# Main-v4_1.net
KiCad netlist of a schematic drawn in EAGLE
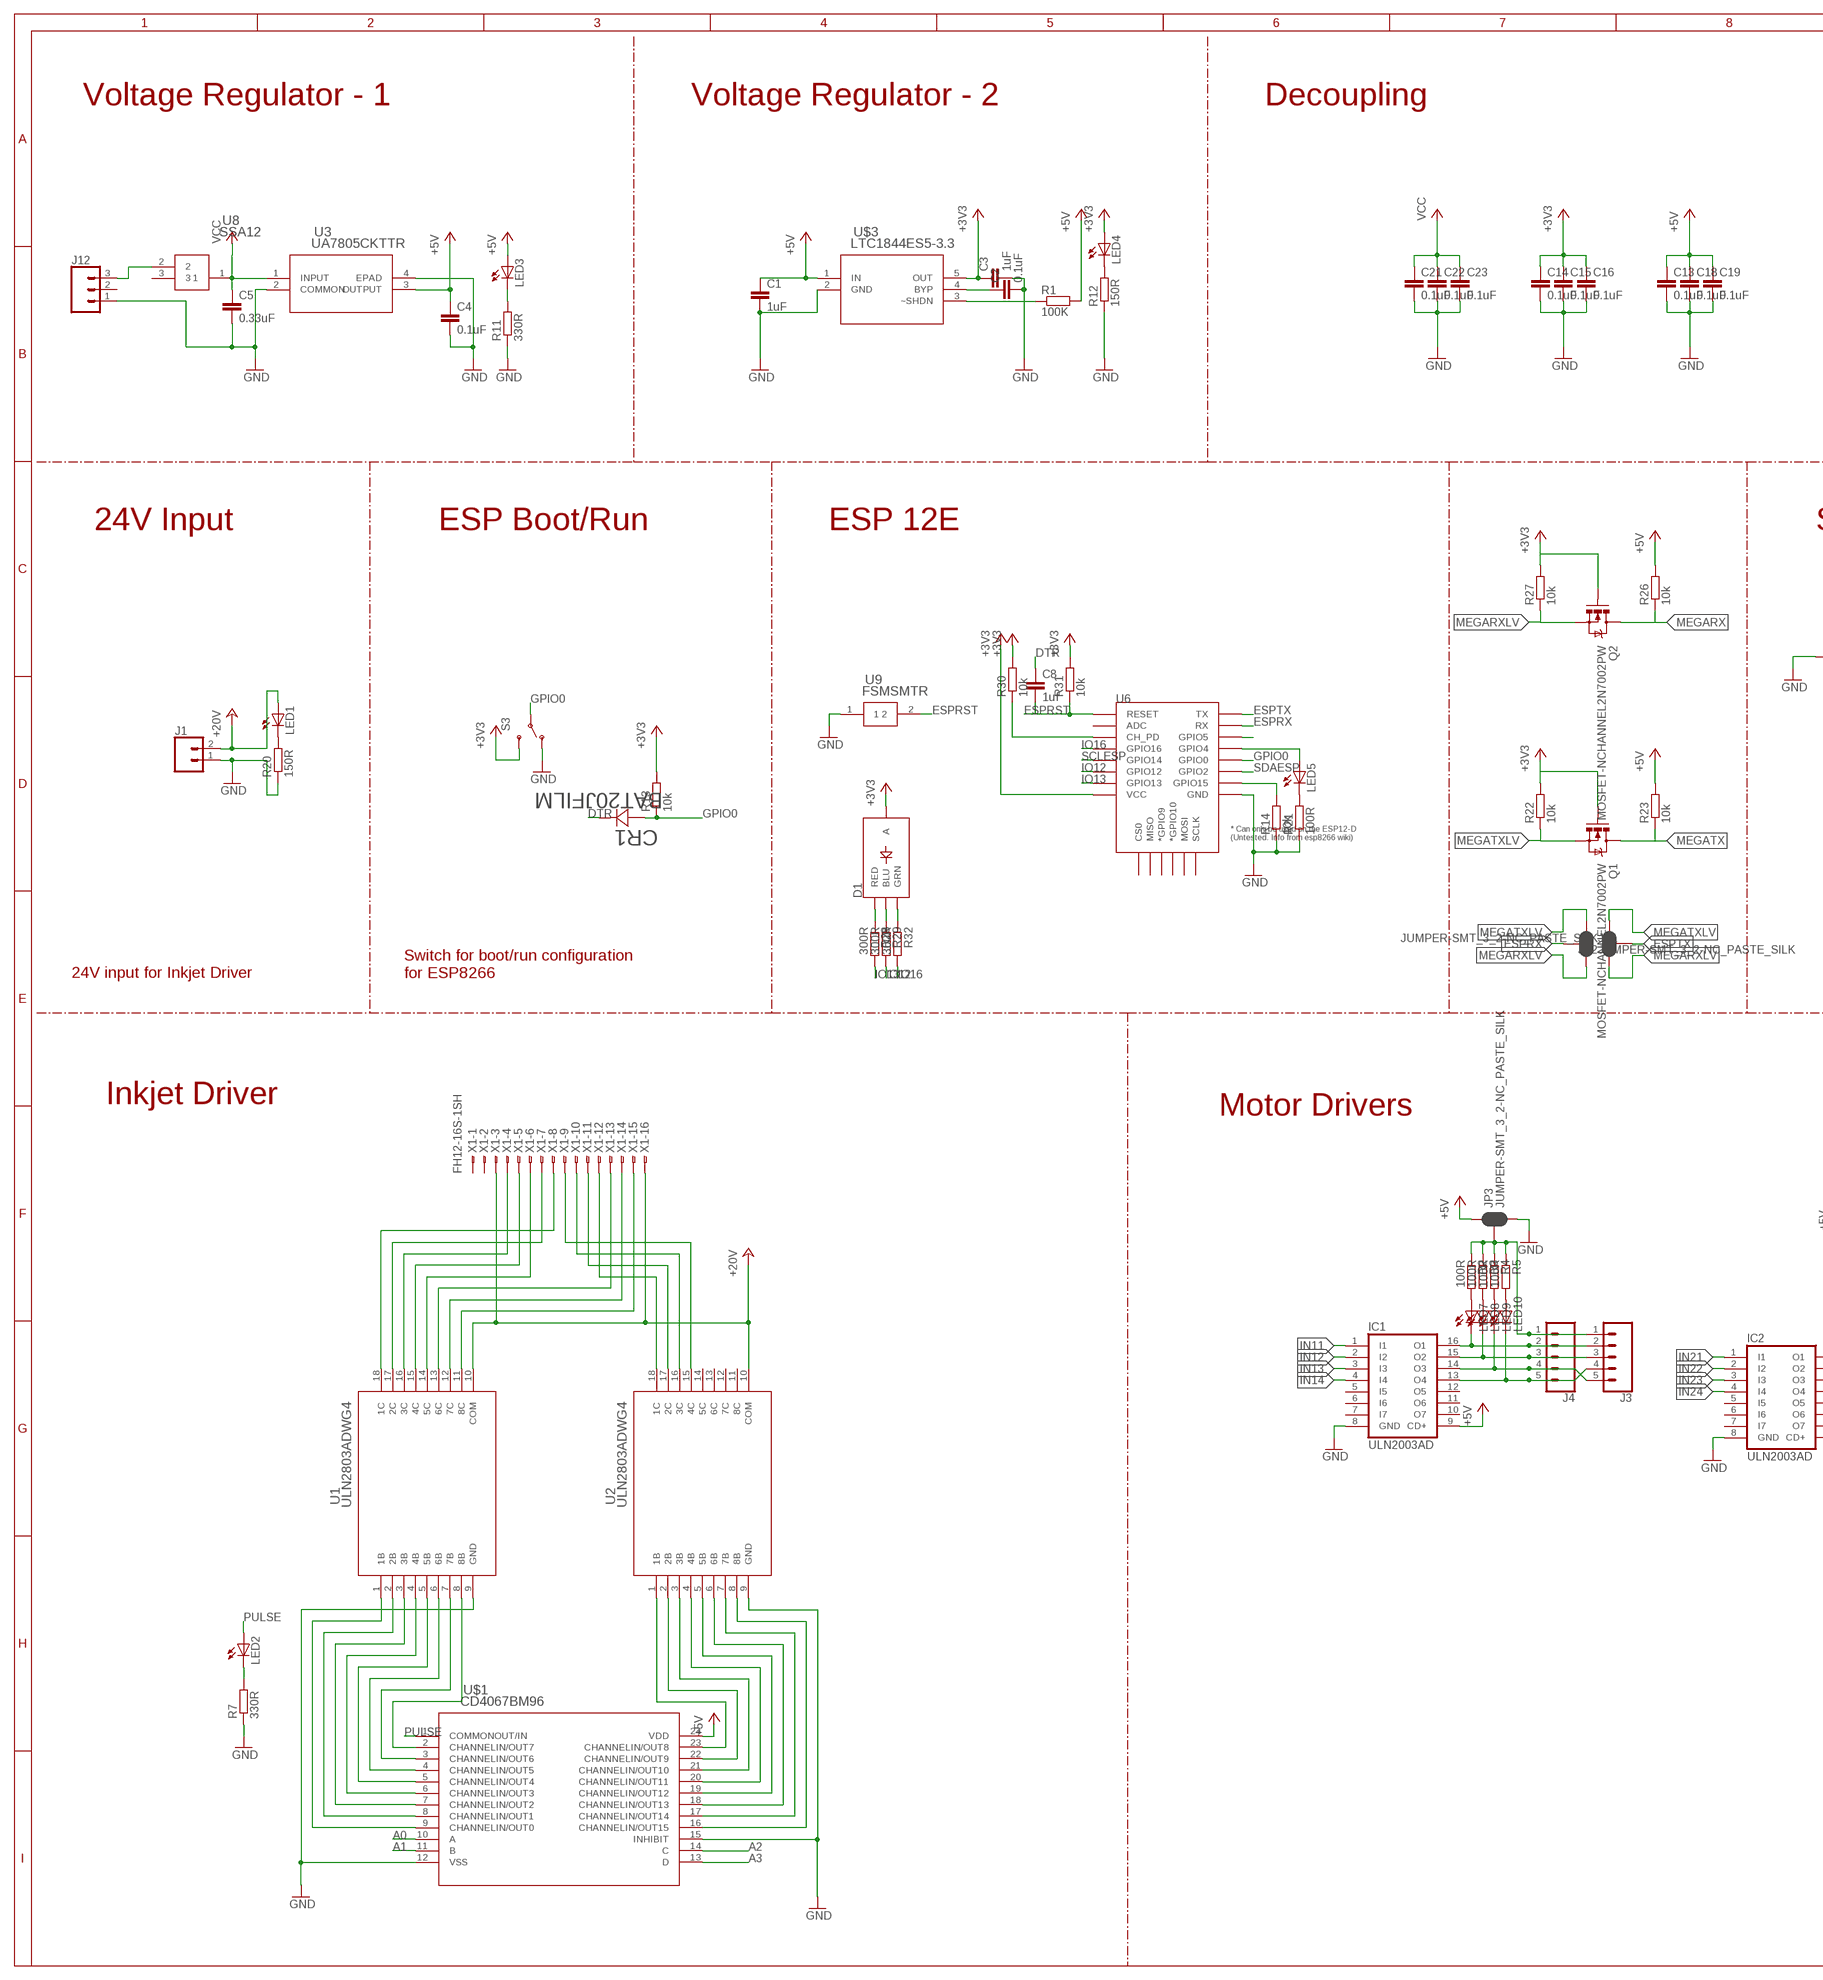
[diagram p0: schematic, sheet 1, part 1 of 3]
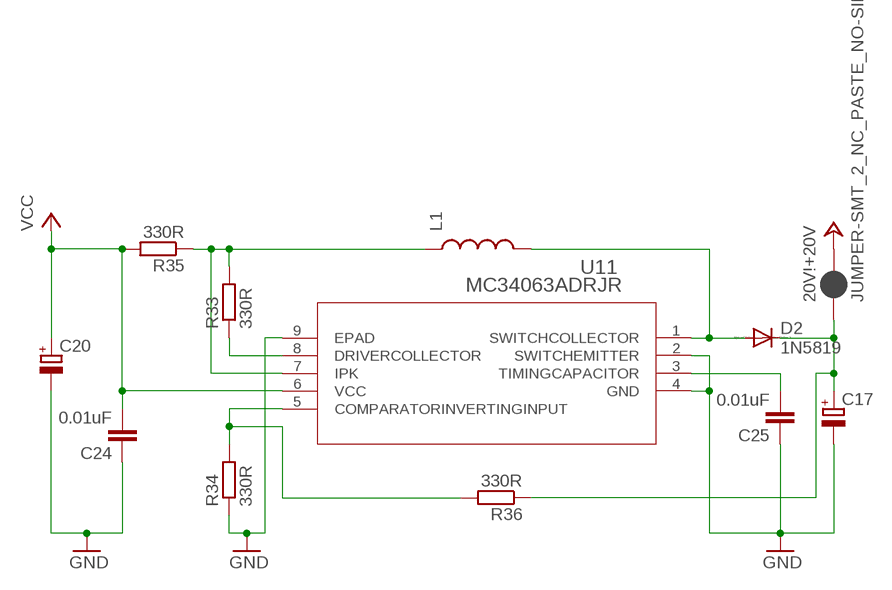
[diagram p1: schematic, sheet 1, part 2 of 3]
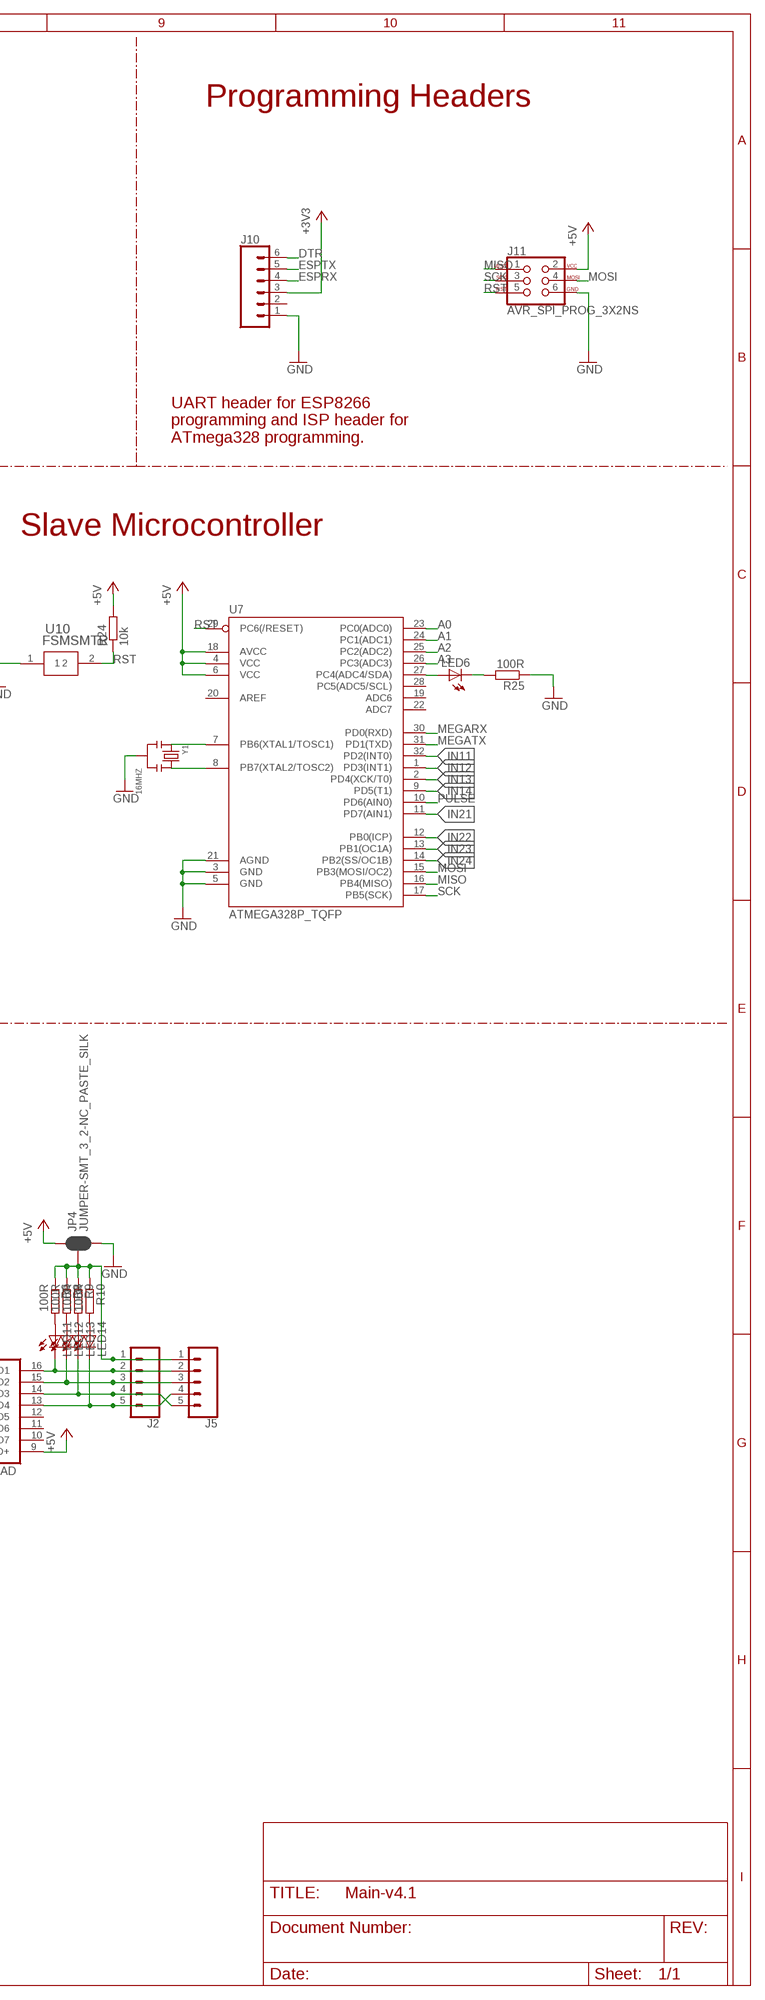
[diagram p2: schematic, sheet 1, part 3 of 3]

(export (version "E")
  (design (tool "Eeschema 10.0.6"))
  (components
    (comp (ref "20V!")
      (value "JUMPER-SMT_2_NC_PASTE_NO-SILK")
      (footprint "eagle-import:SMT-JUMPER_2_NC_PASTE_NO-SILK")
      (libsource (lib "eagle-import") (part "JUMPER-SMT_2_NC_PASTE_NO-SILK"))
    )
    (comp (ref "C1")
      (value "1uF")
      (footprint "eagle-import:C0603")
      (libsource (lib "eagle-import") (part "C-EUC0603"))
    )
    (comp (ref "C2")
      (value "0.1uF")
      (footprint "eagle-import:C0603")
      (libsource (lib "eagle-import") (part "C-EUC0603"))
    )
    (comp (ref "C3")
      (value "1uF")
      (footprint "eagle-import:C0603")
      (libsource (lib "eagle-import") (part "C-EUC0603"))
    )
    (comp (ref "C4")
      (value "0.1uF")
      (footprint "eagle-import:C0603")
      (libsource (lib "eagle-import") (part "C-EUC0603"))
    )
    (comp (ref "C5")
      (value "0.33uF")
      (footprint "eagle-import:C0603")
      (libsource (lib "eagle-import") (part "C-EUC0603"))
    )
    (comp (ref "C8")
      (value "1uf")
      (footprint "eagle-import:C0603")
      (libsource (lib "eagle-import") (part "resistor_348_C-EUC0603"))
    )
    (comp (ref "C13")
      (value "0.1uF")
      (footprint "eagle-import:C0603")
      (libsource (lib "eagle-import") (part "C-EUC0603"))
    )
    (comp (ref "C14")
      (value "0.1uF")
      (footprint "eagle-import:C0603")
      (libsource (lib "eagle-import") (part "C-EUC0603"))
    )
    (comp (ref "C15")
      (value "0.1uF")
      (footprint "eagle-import:C0603")
      (libsource (lib "eagle-import") (part "C-EUC0603"))
    )
    (comp (ref "C16")
      (value "0.1uF")
      (footprint "eagle-import:C0603")
      (libsource (lib "eagle-import") (part "C-EUC0603"))
    )
    (comp (ref "C17")
      (value "CPOL-EU153CLV-1010")
      (footprint "eagle-import:153CLV-1010")
      (libsource (lib "eagle-import") (part "CPOL-EU153CLV-1010"))
    )
    (comp (ref "C18")
      (value "0.1uF")
      (footprint "eagle-import:C0603")
      (libsource (lib "eagle-import") (part "C-EUC0603"))
    )
    (comp (ref "C19")
      (value "0.1uF")
      (footprint "eagle-import:C0603")
      (libsource (lib "eagle-import") (part "C-EUC0603"))
    )
    (comp (ref "C20")
      (value "CPOL-EUSMCC")
      (footprint "eagle-import:SMC_C")
      (libsource (lib "eagle-import") (part "CPOL-EUSMCC"))
    )
    (comp (ref "C21")
      (value "0.1uF")
      (footprint "eagle-import:C0603")
      (libsource (lib "eagle-import") (part "C-EUC0603"))
    )
    (comp (ref "C22")
      (value "0.1uF")
      (footprint "eagle-import:C0603")
      (libsource (lib "eagle-import") (part "C-EUC0603"))
    )
    (comp (ref "C23")
      (value "0.1uF")
      (footprint "eagle-import:C0603")
      (libsource (lib "eagle-import") (part "C-EUC0603"))
    )
    (comp (ref "C24")
      (value "0.01uF")
      (footprint "eagle-import:C0603K")
      (libsource (lib "eagle-import") (part "resistor_348_C-EUC0603K"))
    )
    (comp (ref "C25")
      (value "0.01uF")
      (footprint "eagle-import:C0603K")
      (libsource (lib "eagle-import") (part "resistor_348_C-EUC0603K"))
    )
    (comp (ref "CR1")
      (value "BAT20JFILM")
      (footprint "eagle-import:SOD-323")
      (libsource (lib "eagle-import") (part "BAT20JFILM"))
    )
    (comp (ref "D1")
      (value "LED-RGB-CASMD")
      (footprint "eagle-import:LED-TRICOLOR-SMD")
      (libsource (lib "eagle-import") (part "LED-RGB-CASMD"))
    )
    (comp (ref "D2")
      (value "1N5819")
      (footprint "eagle-import:SOD123")
      (libsource (lib "eagle-import") (part "1N5819"))
    )
    (comp (ref "IC1")
      (value "ULN2003AD")
      (footprint "eagle-import:SO16")
      (libsource (lib "eagle-import") (part "ULN2003AD"))
    )
    (comp (ref "IC2")
      (value "ULN2003AD")
      (footprint "eagle-import:SO16")
      (libsource (lib "eagle-import") (part "ULN2003AD"))
    )
    (comp (ref "J1")
      (value "CONN_02")
      (footprint "eagle-import:1X02")
      (libsource (lib "eagle-import") (part "CONN_02"))
    )
    (comp (ref "J2")
      (value "CONN_05")
      (footprint "eagle-import:1X05")
      (libsource (lib "eagle-import") (part "CONN_05"))
    )
    (comp (ref "J3")
      (value "CONN_05")
      (footprint "eagle-import:1X05")
      (libsource (lib "eagle-import") (part "CONN_05"))
    )
    (comp (ref "J4")
      (value "CONN_05")
      (footprint "eagle-import:1X05")
      (libsource (lib "eagle-import") (part "CONN_05"))
    )
    (comp (ref "J5")
      (value "CONN_05")
      (footprint "eagle-import:1X05")
      (libsource (lib "eagle-import") (part "CONN_05"))
    )
    (comp (ref "J10")
      (value "CONN_06NO_SILK_NO_POP")
      (footprint "eagle-import:1X06_NO_SILK")
      (libsource (lib "eagle-import") (part "CONN_06NO_SILK_NO_POP"))
    )
    (comp (ref "J11")
      (value "AVR_SPI_PROG_3X2NS")
      (footprint "eagle-import:2X3-NS")
      (libsource (lib "eagle-import") (part "AVR_SPI_PROG_3X2NS"))
    )
    (comp (ref "J12")
      (value "CONN_03")
      (footprint "eagle-import:1X03")
      (libsource (lib "eagle-import") (part "CONN_03"))
    )
    (comp (ref "JP1")
      (value "JUMPER-SMT_3_2-NC_PASTE_SILK")
      (footprint "eagle-import:SMT-JUMPER_3_2-NC_PASTE_SILK")
      (libsource (lib "eagle-import") (part "JUMPER-SMT_3_2-NC_PASTE_SILK"))
    )
    (comp (ref "JP2")
      (value "JUMPER-SMT_3_2-NC_PASTE_SILK")
      (footprint "eagle-import:SMT-JUMPER_3_2-NC_PASTE_SILK")
      (libsource (lib "eagle-import") (part "JUMPER-SMT_3_2-NC_PASTE_SILK"))
    )
    (comp (ref "JP3")
      (value "JUMPER-SMT_3_2-NC_PASTE_SILK")
      (footprint "eagle-import:SMT-JUMPER_3_2-NC_PASTE_SILK")
      (libsource (lib "eagle-import") (part "JUMPER-SMT_3_2-NC_PASTE_SILK"))
    )
    (comp (ref "JP4")
      (value "JUMPER-SMT_3_2-NC_PASTE_SILK")
      (footprint "eagle-import:SMT-JUMPER_3_2-NC_PASTE_SILK")
      (libsource (lib "eagle-import") (part "JUMPER-SMT_3_2-NC_PASTE_SILK"))
    )
    (comp (ref "L1")
      (value "INDUCTORCR54")
      (footprint "eagle-import:CR54")
      (libsource (lib "eagle-import") (part "INDUCTORCR54"))
    )
    (comp (ref "LED1")
      (value "LEDSML0603")
      (footprint "eagle-import:SML0603")
      (libsource (lib "eagle-import") (part "LEDSML0603"))
    )
    (comp (ref "LED2")
      (value "LEDSML0603")
      (footprint "eagle-import:SML0603")
      (libsource (lib "eagle-import") (part "LEDSML0603"))
    )
    (comp (ref "LED3")
      (value "LEDSML0603")
      (footprint "eagle-import:SML0603")
      (libsource (lib "eagle-import") (part "LEDSML0603"))
    )
    (comp (ref "LED4")
      (value "LEDSML0603")
      (footprint "eagle-import:SML0603")
      (libsource (lib "eagle-import") (part "LEDSML0603"))
    )
    (comp (ref "LED5")
      (value "LEDSML0603")
      (footprint "eagle-import:SML0603")
      (libsource (lib "eagle-import") (part "LEDSML0603"))
    )
    (comp (ref "LED6")
      (value "LEDSML0603")
      (footprint "eagle-import:SML0603")
      (libsource (lib "eagle-import") (part "LEDSML0603"))
    )
    (comp (ref "LED7")
      (value "LEDSML0603")
      (footprint "eagle-import:SML0603")
      (libsource (lib "eagle-import") (part "LEDSML0603"))
    )
    (comp (ref "LED8")
      (value "LEDSML0603")
      (footprint "eagle-import:SML0603")
      (libsource (lib "eagle-import") (part "LEDSML0603"))
    )
    (comp (ref "LED9")
      (value "LEDSML0603")
      (footprint "eagle-import:SML0603")
      (libsource (lib "eagle-import") (part "LEDSML0603"))
    )
    (comp (ref "LED10")
      (value "LEDSML0603")
      (footprint "eagle-import:SML0603")
      (libsource (lib "eagle-import") (part "LEDSML0603"))
    )
    (comp (ref "LED11")
      (value "LEDSML0603")
      (footprint "eagle-import:SML0603")
      (libsource (lib "eagle-import") (part "LEDSML0603"))
    )
    (comp (ref "LED12")
      (value "LEDSML0603")
      (footprint "eagle-import:SML0603")
      (libsource (lib "eagle-import") (part "LEDSML0603"))
    )
    (comp (ref "LED13")
      (value "LEDSML0603")
      (footprint "eagle-import:SML0603")
      (libsource (lib "eagle-import") (part "LEDSML0603"))
    )
    (comp (ref "LED14")
      (value "LEDSML0603")
      (footprint "eagle-import:SML0603")
      (libsource (lib "eagle-import") (part "LEDSML0603"))
    )
    (comp (ref "Q1")
      (value "MOSFET-NCHANNEL2N7002PW")
      (footprint "eagle-import:SOT323")
      (libsource (lib "eagle-import") (part "MOSFET-NCHANNEL2N7002PW"))
    )
    (comp (ref "Q2")
      (value "MOSFET-NCHANNEL2N7002PW")
      (footprint "eagle-import:SOT323")
      (libsource (lib "eagle-import") (part "MOSFET-NCHANNEL2N7002PW"))
    )
    (comp (ref "R1")
      (value "100K")
      (footprint "eagle-import:R0603")
      (libsource (lib "eagle-import") (part "R-EU_R0603"))
    )
    (comp (ref "R2")
      (value "100R")
      (footprint "eagle-import:R0603")
      (libsource (lib "eagle-import") (part "R-EU_R0603"))
    )
    (comp (ref "R3")
      (value "100R")
      (footprint "eagle-import:R0603")
      (libsource (lib "eagle-import") (part "R-EU_R0603"))
    )
    (comp (ref "R4")
      (value "100R")
      (footprint "eagle-import:R0603")
      (libsource (lib "eagle-import") (part "R-EU_R0603"))
    )
    (comp (ref "R5")
      (value "100R")
      (footprint "eagle-import:R0603")
      (libsource (lib "eagle-import") (part "R-EU_R0603"))
    )
    (comp (ref "R6")
      (value "100R")
      (footprint "eagle-import:R0603")
      (libsource (lib "eagle-import") (part "R-EU_R0603"))
    )
    (comp (ref "R7")
      (value "330R")
      (footprint "eagle-import:R0603")
      (libsource (lib "eagle-import") (part "R-EU_R0603"))
    )
    (comp (ref "R8")
      (value "100R")
      (footprint "eagle-import:R0603")
      (libsource (lib "eagle-import") (part "R-EU_R0603"))
    )
    (comp (ref "R9")
      (value "100R")
      (footprint "eagle-import:R0603")
      (libsource (lib "eagle-import") (part "R-EU_R0603"))
    )
    (comp (ref "R10")
      (value "100R")
      (footprint "eagle-import:R0603")
      (libsource (lib "eagle-import") (part "R-EU_R0603"))
    )
    (comp (ref "R11")
      (value "330R")
      (footprint "eagle-import:R0603")
      (libsource (lib "eagle-import") (part "R-EU_R0603"))
    )
    (comp (ref "R12")
      (value "150R")
      (footprint "eagle-import:R0603")
      (libsource (lib "eagle-import") (part "R-EU_R0603"))
    )
    (comp (ref "R13")
      (value "10k")
      (footprint "eagle-import:R0603")
      (libsource (lib "eagle-import") (part "R-EU_R0603"))
    )
    (comp (ref "R14")
      (value "10k")
      (footprint "eagle-import:R0603")
      (libsource (lib "eagle-import") (part "R-EU_R0603"))
    )
    (comp (ref "R20")
      (value "150R")
      (footprint "eagle-import:R0603")
      (libsource (lib "eagle-import") (part "R-EU_R0603"))
    )
    (comp (ref "R21")
      (value "100R")
      (footprint "eagle-import:R0603")
      (libsource (lib "eagle-import") (part "R-EU_R0603"))
    )
    (comp (ref "R22")
      (value "10k")
      (footprint "eagle-import:R0603")
      (libsource (lib "eagle-import") (part "R-EU_R0603"))
    )
    (comp (ref "R23")
      (value "10k")
      (footprint "eagle-import:R0603")
      (libsource (lib "eagle-import") (part "R-EU_R0603"))
    )
    (comp (ref "R24")
      (value "10k")
      (footprint "eagle-import:R0603")
      (libsource (lib "eagle-import") (part "R-EU_R0603"))
    )
    (comp (ref "R25")
      (value "100R")
      (footprint "eagle-import:R0603")
      (libsource (lib "eagle-import") (part "R-EU_R0603"))
    )
    (comp (ref "R26")
      (value "10k")
      (footprint "eagle-import:R0603")
      (libsource (lib "eagle-import") (part "R-EU_R0603"))
    )
    (comp (ref "R27")
      (value "10k")
      (footprint "eagle-import:R0603")
      (libsource (lib "eagle-import") (part "R-EU_R0603"))
    )
    (comp (ref "R28")
      (value "300R")
      (footprint "eagle-import:R0603")
      (libsource (lib "eagle-import") (part "R-EU_R0603"))
    )
    (comp (ref "R29")
      (value "300R")
      (footprint "eagle-import:R0603")
      (libsource (lib "eagle-import") (part "R-EU_R0603"))
    )
    (comp (ref "R30")
      (value "10k")
      (footprint "eagle-import:R0603")
      (libsource (lib "eagle-import") (part "R-EU_R0603"))
    )
    (comp (ref "R31")
      (value "10k")
      (footprint "eagle-import:R0603")
      (libsource (lib "eagle-import") (part "R-EU_R0603"))
    )
    (comp (ref "R32")
      (value "300R")
      (footprint "eagle-import:R0603")
      (libsource (lib "eagle-import") (part "R-EU_R0603"))
    )
    (comp (ref "R33")
      (value "330R")
      (footprint "eagle-import:R0603")
      (libsource (lib "eagle-import") (part "R-EU_R0603"))
    )
    (comp (ref "R34")
      (value "330R")
      (footprint "eagle-import:R0603")
      (libsource (lib "eagle-import") (part "R-EU_R0603"))
    )
    (comp (ref "R35")
      (value "330R")
      (footprint "eagle-import:R0603")
      (libsource (lib "eagle-import") (part "R-EU_R0603"))
    )
    (comp (ref "R36")
      (value "330R")
      (footprint "eagle-import:R0603")
      (libsource (lib "eagle-import") (part "R-EU_R0603"))
    )
    (comp (ref "S3")
      (value "SWITCH-SPDT-SMD-A")
      (footprint "eagle-import:SWITCH-SPST-SMD-A")
      (libsource (lib "eagle-import") (part "SWITCH-SPDT-SMD-A"))
    )
    (comp (ref "U$1")
      (value "CD4067BM96")
      (footprint "eagle-import:DW24")
      (fields (field (name "MANUFACTURER_PART_NUMBER") "CD4067B_DW_24"))
      (libsource (lib "eagle-import") (part "CD4067BM96"))
    )
    (comp (ref "U$3")
      (value "LTC1844ES5-3.3")
      (footprint "eagle-import:TSOT-23_S5")
      (libsource (lib "eagle-import") (part "LTC1844ES5-3.3"))
    )
    (comp (ref "U1")
      (value "ULN2803ADWG4")
      (footprint "eagle-import:DW18")
      (libsource (lib "eagle-import") (part "ULN2803ADWG4"))
    )
    (comp (ref "U2")
      (value "ULN2803ADWG4")
      (footprint "eagle-import:DW18")
      (libsource (lib "eagle-import") (part "ULN2803ADWG4"))
    )
    (comp (ref "U3")
      (value "UA7805CKTTR")
      (footprint "eagle-import:KTT3_6P22X6P6")
      (libsource (lib "eagle-import") (part "UA7805CKTTR"))
    )
    (comp (ref "U6")
      (value "ESP12ESMD")
      (footprint "eagle-import:ESP12E-SMD")
      (libsource (lib "eagle-import") (part "ESP12ESMD"))
    )
    (comp (ref "U7")
      (value "ATMEGA328P_TQFP")
      (footprint "eagle-import:TQFP32-08")
      (libsource (lib "eagle-import") (part "ATMEGA328P_TQFP"))
    )
    (comp (ref "U8")
      (value "SSA12")
      (footprint "eagle-import:SWSIP3-P98")
      (libsource (lib "eagle-import") (part "SSA12"))
    )
    (comp (ref "U9")
      (value "FSMSMTR")
      (footprint "eagle-import:SWITCH_FSMSMTR")
      (libsource (lib "eagle-import") (part "FSMSMTR"))
    )
    (comp (ref "U10")
      (value "FSMSMTR")
      (footprint "eagle-import:SWITCH_FSMSMTR")
      (libsource (lib "eagle-import") (part "FSMSMTR"))
    )
    (comp (ref "U11")
      (value "MC34063ADRJR")
      (footprint "eagle-import:DRJ8_2P2X3")
      (libsource (lib "eagle-import") (part "MC34063ADRJR"))
    )
    (comp (ref "X1")
      (value "FH12-16S-1SH")
      (footprint "eagle-import:FH12-16S-1SH")
      (libsource (lib "eagle-import") (part "FH12-16S-1SH"))
    )
    (comp (ref "Y1")
      (value "16MHZ")
      (footprint "eagle-import:X3-SMD-3.6X1.3X0.8MM")
      (fields (field (name "MPN") "CSTCE16M0V53-R0"))
      (libsource (lib "eagle-import") (part "SMD-RESONATOR-16MHZ-15PF-0.5%-40R(3P-3.2X1.3MM)"))
    )
  )
  (nets
    (net (code "1") (name "+3V3") (class "Default")
      (node (ref "C14") (pin "1") (pinfunction "1_1") (pintype "passive"))
      (node (ref "C15") (pin "1") (pinfunction "1_1") (pintype "passive"))
      (node (ref "C16") (pin "1") (pinfunction "1_1") (pintype "passive"))
      (node (ref "C3") (pin "1") (pinfunction "1_1") (pintype "passive"))
      (node (ref "D1") (pin "A") (pinfunction "A_A") (pintype "bidirectional"))
      (node (ref "J10") (pin "3") (pinfunction "3_3") (pintype "passive"))
      (node (ref "LED4") (pin "A") (pinfunction "A_A") (pintype "passive"))
      (node (ref "Q1") (pin "1") (pinfunction "G_1") (pintype "passive"))
      (node (ref "Q2") (pin "1") (pinfunction "G_1") (pintype "passive"))
      (node (ref "R13") (pin "2") (pinfunction "2_2") (pintype "passive"))
      (node (ref "R22") (pin "2") (pinfunction "2_2") (pintype "passive"))
      (node (ref "R27") (pin "2") (pinfunction "2_2") (pintype "passive"))
      (node (ref "R30") (pin "2") (pinfunction "2_2") (pintype "passive"))
      (node (ref "R31") (pin "2") (pinfunction "2_2") (pintype "passive"))
      (node (ref "S3") (pin "3") (pinfunction "S_3") (pintype "passive"))
      (node (ref "U$3") (pin "5") (pinfunction "OUT_5") (pintype "passive"))
      (node (ref "U6") (pin "VCC") (pinfunction "VCC_VCC") (pintype "bidirectional"))
    )
    (net (code "2") (name "+5V") (class "Default")
      (node (ref "C1") (pin "1") (pinfunction "1_1") (pintype "passive"))
      (node (ref "C13") (pin "1") (pinfunction "1_1") (pintype "passive"))
      (node (ref "C18") (pin "1") (pinfunction "1_1") (pintype "passive"))
      (node (ref "C19") (pin "1") (pinfunction "1_1") (pintype "passive"))
      (node (ref "C4") (pin "1") (pinfunction "1_1") (pintype "passive"))
      (node (ref "IC1") (pin "9") (pinfunction "CD+_9") (pintype "passive"))
      (node (ref "IC2") (pin "9") (pinfunction "CD+_9") (pintype "passive"))
      (node (ref "J11") (pin "2") (pinfunction "2_2") (pintype "passive"))
      (node (ref "JP3") (pin "1") (pinfunction "1_1") (pintype "passive"))
      (node (ref "JP4") (pin "1") (pinfunction "1_1") (pintype "passive"))
      (node (ref "LED3") (pin "A") (pinfunction "A_A") (pintype "passive"))
      (node (ref "R1") (pin "2") (pinfunction "2_2") (pintype "passive"))
      (node (ref "R23") (pin "2") (pinfunction "2_2") (pintype "passive"))
      (node (ref "R24") (pin "2") (pinfunction "2_2") (pintype "passive"))
      (node (ref "R26") (pin "2") (pinfunction "2_2") (pintype "passive"))
      (node (ref "U$1") (pin "24") (pinfunction "VDD_24") (pintype "power_in"))
      (node (ref "U$3") (pin "1") (pinfunction "IN_1") (pintype "passive"))
      (node (ref "U3") (pin "3") (pinfunction "OUTPUT_3") (pintype "output"))
      (node (ref "U7") (pin "18") (pinfunction "AVCC_18") (pintype "bidirectional"))
      (node (ref "U7") (pin "4") (pinfunction "VCC_4") (pintype "bidirectional"))
      (node (ref "U7") (pin "6") (pinfunction "VCC_6") (pintype "bidirectional"))
    )
    (net (code "3") (name "+20V") (class "Default")
      (node (ref "20V!") (pin "2") (pinfunction "2_2") (pintype "passive"))
      (node (ref "J1") (pin "2") (pinfunction "2_2") (pintype "passive"))
      (node (ref "LED1") (pin "A") (pinfunction "A_A") (pintype "passive"))
      (node (ref "U1") (pin "10") (pinfunction "COM_10") (pintype "passive"))
      (node (ref "U2") (pin "10") (pinfunction "COM_10") (pintype "passive"))
      (node (ref "X1") (pin "16") (pinfunction "1_16") (pintype "passive"))
      (node (ref "X1") (pin "3") (pinfunction "1_3") (pintype "passive"))
    )
    (net (code "4") (name "/A0") (class "Default")
      (node (ref "U$1") (pin "10") (pinfunction "A_10") (pintype "passive"))
      (node (ref "U7") (pin "23") (pinfunction "PC0(ADC0)_23") (pintype "bidirectional"))
    )
    (net (code "5") (name "/A1") (class "Default")
      (node (ref "U$1") (pin "11") (pinfunction "B_11") (pintype "passive"))
      (node (ref "U7") (pin "24") (pinfunction "PC1(ADC1)_24") (pintype "bidirectional"))
    )
    (net (code "6") (name "/A2") (class "Default")
      (node (ref "U$1") (pin "14") (pinfunction "C_14") (pintype "passive"))
      (node (ref "U7") (pin "25") (pinfunction "PC2(ADC2)_25") (pintype "bidirectional"))
    )
    (net (code "7") (name "/A3") (class "Default")
      (node (ref "U$1") (pin "13") (pinfunction "D_13") (pintype "passive"))
      (node (ref "U7") (pin "26") (pinfunction "PC3(ADC3)_26") (pintype "bidirectional"))
    )
    (net (code "8") (name "/DTR") (class "Default")
      (node (ref "C8") (pin "1") (pinfunction "1_1") (pintype "passive"))
      (node (ref "CR1") (pin "1") (pinfunction "11_1") (pintype "passive"))
      (node (ref "J10") (pin "6") (pinfunction "6_6") (pintype "passive"))
    )
    (net (code "9") (name "/ESPRST") (class "Default")
      (node (ref "C8") (pin "2") (pinfunction "2_2") (pintype "passive"))
      (node (ref "R31") (pin "1") (pinfunction "1_1") (pintype "passive"))
      (node (ref "U6") (pin "RESET") (pinfunction "RESET_RESET") (pintype "bidirectional"))
      (node (ref "U9") (pin "2") (pinfunction "2_2") (pintype "passive"))
    )
    (net (code "10") (name "/GPIO0") (class "Default")
      (node (ref "CR1") (pin "2") (pinfunction "22_2") (pintype "passive"))
      (node (ref "R13") (pin "1") (pinfunction "1_1") (pintype "passive"))
      (node (ref "S3") (pin "2") (pinfunction "P_2") (pintype "passive"))
      (node (ref "U6") (pin "GPIO0") (pinfunction "GPIO0_GPIO0") (pintype "bidirectional"))
    )
    (net (code "11") (name "/IO12") (class "Default")
      (node (ref "R29") (pin "2") (pinfunction "2_2") (pintype "passive"))
      (node (ref "U6") (pin "GPIO12") (pinfunction "GPIO12_GPIO12") (pintype "bidirectional"))
    )
    (net (code "12") (name "/IO13") (class "Default")
      (node (ref "R28") (pin "2") (pinfunction "2_2") (pintype "passive"))
      (node (ref "U6") (pin "GPIO13") (pinfunction "GPIO13_GPIO13") (pintype "bidirectional"))
    )
    (net (code "13") (name "/IO16") (class "Default")
      (node (ref "R32") (pin "2") (pinfunction "2_2") (pintype "passive"))
      (node (ref "U6") (pin "GPIO16") (pinfunction "GPIO16_GPIO16") (pintype "bidirectional"))
    )
    (net (code "14") (name "/MISO") (class "Default")
      (node (ref "J11") (pin "1") (pinfunction "1_1") (pintype "passive"))
      (node (ref "U7") (pin "16") (pinfunction "PB4(MISO)_16") (pintype "bidirectional"))
    )
    (net (code "15") (name "/MOSI") (class "Default")
      (node (ref "J11") (pin "4") (pinfunction "4_4") (pintype "passive"))
      (node (ref "U7") (pin "15") (pinfunction "PB3(MOSI/OC2)_15") (pintype "bidirectional"))
    )
    (net (code "16") (name "/PULSE") (class "Default")
      (node (ref "LED2") (pin "A") (pinfunction "A_A") (pintype "passive"))
      (node (ref "U$1") (pin "1") (pinfunction "COMMONOUT/IN_1") (pintype "bidirectional"))
      (node (ref "U7") (pin "10") (pinfunction "PD6(AIN0)_10") (pintype "bidirectional"))
    )
    (net (code "17") (name "/RST") (class "Default")
      (node (ref "J11") (pin "5") (pinfunction "5_5") (pintype "passive"))
      (node (ref "R24") (pin "1") (pinfunction "1_1") (pintype "passive"))
      (node (ref "U10") (pin "2") (pinfunction "2_2") (pintype "passive"))
      (node (ref "U7") (pin "29") (pinfunction "PC6(/RESET)_29") (pintype "bidirectional"))
    )
    (net (code "18") (name "/SCK") (class "Default")
      (node (ref "J11") (pin "3") (pinfunction "3_3") (pintype "passive"))
      (node (ref "U7") (pin "17") (pinfunction "PB5(SCK)_17") (pintype "bidirectional"))
    )
    (net (code "19") (name "/SCLESP") (class "Default")
      (node (ref "U6") (pin "GPIO14") (pinfunction "GPIO14_GPIO14") (pintype "bidirectional"))
    )
    (net (code "20") (name "/SDAESP") (class "Default")
      (node (ref "U6") (pin "GPIO2") (pinfunction "GPIO2_GPIO2") (pintype "bidirectional"))
    )
    (net (code "21") (name "ESPRX") (class "Default")
      (node (ref "J10") (pin "4") (pinfunction "4_4") (pintype "passive"))
      (node (ref "JP1") (pin "2") (pinfunction "2_2") (pintype "passive"))
      (node (ref "U6") (pin "RXD0") (pinfunction "RX_RXD0") (pintype "bidirectional"))
    )
    (net (code "22") (name "ESPTX") (class "Default")
      (node (ref "J10") (pin "5") (pinfunction "5_5") (pintype "passive"))
      (node (ref "JP2") (pin "2") (pinfunction "2_2") (pintype "passive"))
      (node (ref "U6") (pin "TXD0") (pinfunction "TX_TXD0") (pintype "bidirectional"))
    )
    (net (code "23") (name "GND") (class "Default")
      (node (ref "C1") (pin "2") (pinfunction "2_2") (pintype "passive"))
      (node (ref "C13") (pin "2") (pinfunction "2_2") (pintype "passive"))
      (node (ref "C14") (pin "2") (pinfunction "2_2") (pintype "passive"))
      (node (ref "C15") (pin "2") (pinfunction "2_2") (pintype "passive"))
      (node (ref "C16") (pin "2") (pinfunction "2_2") (pintype "passive"))
      (node (ref "C17") (pin "-") (pinfunction "-_-") (pintype "passive"))
      (node (ref "C18") (pin "2") (pinfunction "2_2") (pintype "passive"))
      (node (ref "C19") (pin "2") (pinfunction "2_2") (pintype "passive"))
      (node (ref "C2") (pin "2") (pinfunction "2_2") (pintype "passive"))
      (node (ref "C20") (pin "-") (pinfunction "-_-") (pintype "passive"))
      (node (ref "C21") (pin "2") (pinfunction "2_2") (pintype "passive"))
      (node (ref "C22") (pin "2") (pinfunction "2_2") (pintype "passive"))
      (node (ref "C23") (pin "2") (pinfunction "2_2") (pintype "passive"))
      (node (ref "C24") (pin "1") (pinfunction "1_1") (pintype "passive"))
      (node (ref "C25") (pin "1") (pinfunction "1_1") (pintype "passive"))
      (node (ref "C3") (pin "2") (pinfunction "2_2") (pintype "passive"))
      (node (ref "C4") (pin "2") (pinfunction "2_2") (pintype "passive"))
      (node (ref "C5") (pin "2") (pinfunction "2_2") (pintype "passive"))
      (node (ref "IC1") (pin "8") (pinfunction "GND_8") (pintype "power_in"))
      (node (ref "IC2") (pin "8") (pinfunction "GND_8") (pintype "power_in"))
      (node (ref "J1") (pin "1") (pinfunction "1_1") (pintype "passive"))
      (node (ref "J10") (pin "1") (pinfunction "1_1") (pintype "passive"))
      (node (ref "J11") (pin "6") (pinfunction "6_6") (pintype "passive"))
      (node (ref "J12") (pin "1") (pinfunction "1_1") (pintype "passive"))
      (node (ref "JP3") (pin "3") (pinfunction "3_3") (pintype "passive"))
      (node (ref "JP4") (pin "3") (pinfunction "3_3") (pintype "passive"))
      (node (ref "R11") (pin "1") (pinfunction "1_1") (pintype "passive"))
      (node (ref "R12") (pin "1") (pinfunction "1_1") (pintype "passive"))
      (node (ref "R14") (pin "1") (pinfunction "1_1") (pintype "passive"))
      (node (ref "R20") (pin "1") (pinfunction "1_1") (pintype "passive"))
      (node (ref "R21") (pin "1") (pinfunction "1_1") (pintype "passive"))
      (node (ref "R25") (pin "1") (pinfunction "1_1") (pintype "passive"))
      (node (ref "R34") (pin "1") (pinfunction "1_1") (pintype "passive"))
      (node (ref "R7") (pin "1") (pinfunction "1_1") (pintype "passive"))
      (node (ref "S3") (pin "1") (pinfunction "O_1") (pintype "passive"))
      (node (ref "U$1") (pin "12") (pinfunction "VSS_12") (pintype "power_in"))
      (node (ref "U$1") (pin "15") (pinfunction "INHIBIT_15") (pintype "passive"))
      (node (ref "U$3") (pin "2") (pinfunction "GND_2") (pintype "passive"))
      (node (ref "U1") (pin "9") (pinfunction "GND_9") (pintype "passive"))
      (node (ref "U10") (pin "1") (pinfunction "1_1") (pintype "passive"))
      (node (ref "U11") (pin "2") (pinfunction "SWITCHEMITTER_2") (pintype "passive"))
      (node (ref "U11") (pin "4") (pinfunction "GND_4") (pintype "power_in"))
      (node (ref "U11") (pin "9") (pinfunction "EPAD_9") (pintype "power_in"))
      (node (ref "U2") (pin "9") (pinfunction "GND_9") (pintype "passive"))
      (node (ref "U3") (pin "2") (pinfunction "COMMON_2") (pintype "power_in"))
      (node (ref "U3") (pin "4") (pinfunction "EPAD_4") (pintype "passive"))
      (node (ref "U6") (pin "GND") (pinfunction "GND_GND") (pintype "bidirectional"))
      (node (ref "U7") (pin "21") (pinfunction "AGND_21") (pintype "bidirectional"))
      (node (ref "U7") (pin "3") (pinfunction "GND_3") (pintype "bidirectional"))
      (node (ref "U7") (pin "5") (pinfunction "GND_5") (pintype "bidirectional"))
      (node (ref "U9") (pin "1") (pinfunction "1_1") (pintype "passive"))
      (node (ref "Y1") (pin "2") (pinfunction "2_2") (pintype "passive"))
    )
    (net (code "24") (name "IN11") (class "Default")
      (node (ref "IC1") (pin "1") (pinfunction "I1_1") (pintype "input"))
      (node (ref "U7") (pin "32") (pinfunction "PD2(INT0)_32") (pintype "bidirectional"))
    )
    (net (code "25") (name "IN12") (class "Default")
      (node (ref "IC1") (pin "2") (pinfunction "I2_2") (pintype "input"))
      (node (ref "U7") (pin "1") (pinfunction "PD3(INT1)_1") (pintype "bidirectional"))
    )
    (net (code "26") (name "IN13") (class "Default")
      (node (ref "IC1") (pin "3") (pinfunction "I3_3") (pintype "input"))
      (node (ref "U7") (pin "2") (pinfunction "PD4(XCK/T0)_2") (pintype "bidirectional"))
    )
    (net (code "27") (name "IN14") (class "Default")
      (node (ref "IC1") (pin "4") (pinfunction "I4_4") (pintype "input"))
      (node (ref "U7") (pin "9") (pinfunction "PD5(T1)_9") (pintype "bidirectional"))
    )
    (net (code "28") (name "IN21") (class "Default")
      (node (ref "IC2") (pin "1") (pinfunction "I1_1") (pintype "input"))
      (node (ref "U7") (pin "11") (pinfunction "PD7(AIN1)_11") (pintype "bidirectional"))
    )
    (net (code "29") (name "IN22") (class "Default")
      (node (ref "IC2") (pin "2") (pinfunction "I2_2") (pintype "input"))
      (node (ref "U7") (pin "12") (pinfunction "PB0(ICP)_12") (pintype "bidirectional"))
    )
    (net (code "30") (name "IN23") (class "Default")
      (node (ref "IC2") (pin "3") (pinfunction "I3_3") (pintype "input"))
      (node (ref "U7") (pin "13") (pinfunction "PB1(OC1A)_13") (pintype "bidirectional"))
    )
    (net (code "31") (name "IN24") (class "Default")
      (node (ref "IC2") (pin "4") (pinfunction "I4_4") (pintype "input"))
      (node (ref "U7") (pin "14") (pinfunction "PB2(SS/OC1B)_14") (pintype "bidirectional"))
    )
    (net (code "32") (name "MEGARX") (class "Default")
      (node (ref "Q2") (pin "3") (pinfunction "D_3") (pintype "passive"))
      (node (ref "R26") (pin "1") (pinfunction "1_1") (pintype "passive"))
      (node (ref "U7") (pin "30") (pinfunction "PD0(RXD)_30") (pintype "bidirectional"))
    )
    (net (code "33") (name "MEGARXLV") (class "Default")
      (node (ref "JP1") (pin "3") (pinfunction "3_3") (pintype "passive"))
      (node (ref "JP2") (pin "1") (pinfunction "1_1") (pintype "passive"))
      (node (ref "Q2") (pin "2") (pinfunction "S_2") (pintype "passive"))
      (node (ref "R27") (pin "1") (pinfunction "1_1") (pintype "passive"))
    )
    (net (code "34") (name "MEGATX") (class "Default")
      (node (ref "Q1") (pin "3") (pinfunction "D_3") (pintype "passive"))
      (node (ref "R23") (pin "1") (pinfunction "1_1") (pintype "passive"))
      (node (ref "U7") (pin "31") (pinfunction "PD1(TXD)_31") (pintype "bidirectional"))
    )
    (net (code "35") (name "MEGATXLV") (class "Default")
      (node (ref "JP1") (pin "1") (pinfunction "1_1") (pintype "passive"))
      (node (ref "JP2") (pin "3") (pinfunction "3_3") (pintype "passive"))
      (node (ref "Q1") (pin "2") (pinfunction "S_2") (pintype "passive"))
      (node (ref "R22") (pin "1") (pinfunction "1_1") (pintype "passive"))
    )
    (net (code "36") (name "Net-(20V!-Pad1)") (class "Default")
      (node (ref "20V!") (pin "1") (pinfunction "1_1") (pintype "passive"))
      (node (ref "C17") (pin "+") (pinfunction "+_+") (pintype "passive"))
      (node (ref "D2") (pin "C") (pinfunction "C_C") (pintype "passive"))
      (node (ref "R36") (pin "1") (pinfunction "1_1") (pintype "passive"))
    )
    (net (code "37") (name "Net-(D1-BLU)") (class "Default")
      (node (ref "D1") (pin "B") (pinfunction "BLU_B") (pintype "bidirectional"))
      (node (ref "R29") (pin "1") (pinfunction "1_1") (pintype "passive"))
    )
    (net (code "38") (name "Net-(D1-GRN)") (class "Default")
      (node (ref "D1") (pin "G") (pinfunction "GRN_G") (pintype "bidirectional"))
      (node (ref "R32") (pin "1") (pinfunction "1_1") (pintype "passive"))
    )
    (net (code "39") (name "Net-(D1-RED)") (class "Default")
      (node (ref "D1") (pin "R") (pinfunction "RED_R") (pintype "bidirectional"))
      (node (ref "R28") (pin "1") (pinfunction "1_1") (pintype "passive"))
    )
    (net (code "40") (name "Net-(IC1-O1)") (class "Default")
      (node (ref "IC1") (pin "16") (pinfunction "O1_16") (pintype "open_collector"))
      (node (ref "J3") (pin "2") (pinfunction "2_2") (pintype "passive"))
      (node (ref "J4") (pin "2") (pinfunction "2_2") (pintype "passive"))
      (node (ref "LED7") (pin "C") (pinfunction "C_C") (pintype "passive"))
    )
    (net (code "41") (name "Net-(IC1-O2)") (class "Default")
      (node (ref "IC1") (pin "15") (pinfunction "O2_15") (pintype "open_collector"))
      (node (ref "J3") (pin "3") (pinfunction "3_3") (pintype "passive"))
      (node (ref "J4") (pin "3") (pinfunction "3_3") (pintype "passive"))
      (node (ref "LED8") (pin "C") (pinfunction "C_C") (pintype "passive"))
    )
    (net (code "42") (name "Net-(IC1-O3)") (class "Default")
      (node (ref "IC1") (pin "14") (pinfunction "O3_14") (pintype "open_collector"))
      (node (ref "J3") (pin "5") (pinfunction "5_5") (pintype "passive"))
      (node (ref "J4") (pin "4") (pinfunction "4_4") (pintype "passive"))
      (node (ref "LED9") (pin "C") (pinfunction "C_C") (pintype "passive"))
    )
    (net (code "43") (name "Net-(IC1-O4)") (class "Default")
      (node (ref "IC1") (pin "13") (pinfunction "O4_13") (pintype "open_collector"))
      (node (ref "J3") (pin "4") (pinfunction "4_4") (pintype "passive"))
      (node (ref "J4") (pin "5") (pinfunction "5_5") (pintype "passive"))
      (node (ref "LED10") (pin "C") (pinfunction "C_C") (pintype "passive"))
    )
    (net (code "44") (name "Net-(IC2-O1)") (class "Default")
      (node (ref "IC2") (pin "16") (pinfunction "O1_16") (pintype "open_collector"))
      (node (ref "J2") (pin "2") (pinfunction "2_2") (pintype "passive"))
      (node (ref "J5") (pin "2") (pinfunction "2_2") (pintype "passive"))
      (node (ref "LED11") (pin "C") (pinfunction "C_C") (pintype "passive"))
    )
    (net (code "45") (name "Net-(IC2-O2)") (class "Default")
      (node (ref "IC2") (pin "15") (pinfunction "O2_15") (pintype "open_collector"))
      (node (ref "J2") (pin "3") (pinfunction "3_3") (pintype "passive"))
      (node (ref "J5") (pin "3") (pinfunction "3_3") (pintype "passive"))
      (node (ref "LED12") (pin "C") (pinfunction "C_C") (pintype "passive"))
    )
    (net (code "46") (name "Net-(IC2-O3)") (class "Default")
      (node (ref "IC2") (pin "14") (pinfunction "O3_14") (pintype "open_collector"))
      (node (ref "J2") (pin "4") (pinfunction "4_4") (pintype "passive"))
      (node (ref "J5") (pin "5") (pinfunction "5_5") (pintype "passive"))
      (node (ref "LED13") (pin "C") (pinfunction "C_C") (pintype "passive"))
    )
    (net (code "47") (name "Net-(IC2-O4)") (class "Default")
      (node (ref "IC2") (pin "13") (pinfunction "O4_13") (pintype "open_collector"))
      (node (ref "J2") (pin "5") (pinfunction "5_5") (pintype "passive"))
      (node (ref "J5") (pin "4") (pinfunction "4_4") (pintype "passive"))
      (node (ref "LED14") (pin "C") (pinfunction "C_C") (pintype "passive"))
    )
    (net (code "48") (name "Net-(J2-Pad1)") (class "Default")
      (node (ref "J2") (pin "1") (pinfunction "1_1") (pintype "passive"))
      (node (ref "J5") (pin "1") (pinfunction "1_1") (pintype "passive"))
      (node (ref "JP4") (pin "2") (pinfunction "2_2") (pintype "passive"))
      (node (ref "R10") (pin "1") (pinfunction "1_1") (pintype "passive"))
      (node (ref "R6") (pin "1") (pinfunction "1_1") (pintype "passive"))
      (node (ref "R8") (pin "1") (pinfunction "1_1") (pintype "passive"))
      (node (ref "R9") (pin "1") (pinfunction "1_1") (pintype "passive"))
    )
    (net (code "49") (name "Net-(J3-Pad1)") (class "Default")
      (node (ref "J3") (pin "1") (pinfunction "1_1") (pintype "passive"))
      (node (ref "J4") (pin "1") (pinfunction "1_1") (pintype "passive"))
      (node (ref "JP3") (pin "2") (pinfunction "2_2") (pintype "passive"))
      (node (ref "R2") (pin "1") (pinfunction "1_1") (pintype "passive"))
      (node (ref "R3") (pin "1") (pinfunction "1_1") (pintype "passive"))
      (node (ref "R4") (pin "1") (pinfunction "1_1") (pintype "passive"))
      (node (ref "R5") (pin "1") (pinfunction "1_1") (pintype "passive"))
    )
    (net (code "50") (name "Net-(J12-Pad3)") (class "Default")
      (node (ref "J12") (pin "3") (pinfunction "3_3") (pintype "passive"))
      (node (ref "U8") (pin "2") (pinfunction "2_2") (pintype "passive"))
    )
    (net (code "51") (name "Net-(L1-1)") (class "Default")
      (node (ref "L1") (pin "P$1") (pinfunction "1_P$1") (pintype "passive"))
      (node (ref "R33") (pin "2") (pinfunction "2_2") (pintype "passive"))
      (node (ref "R35") (pin "1") (pinfunction "1_1") (pintype "passive"))
      (node (ref "U11") (pin "7") (pinfunction "IPK_7") (pintype "passive"))
    )
    (net (code "52") (name "Net-(L1-2)") (class "Default")
      (node (ref "D2") (pin "A") (pinfunction "A_A") (pintype "passive"))
      (node (ref "L1") (pin "P$2") (pinfunction "2_P$2") (pintype "passive"))
      (node (ref "U11") (pin "1") (pinfunction "SWITCHCOLLECTOR_1") (pintype "passive"))
    )
    (net (code "53") (name "Net-(LED1-PadC)") (class "Default")
      (node (ref "LED1") (pin "C") (pinfunction "C_C") (pintype "passive"))
      (node (ref "R20") (pin "2") (pinfunction "2_2") (pintype "passive"))
    )
    (net (code "54") (name "Net-(LED2-PadC)") (class "Default")
      (node (ref "LED2") (pin "C") (pinfunction "C_C") (pintype "passive"))
      (node (ref "R7") (pin "2") (pinfunction "2_2") (pintype "passive"))
    )
    (net (code "55") (name "Net-(LED3-PadC)") (class "Default")
      (node (ref "LED3") (pin "C") (pinfunction "C_C") (pintype "passive"))
      (node (ref "R11") (pin "2") (pinfunction "2_2") (pintype "passive"))
    )
    (net (code "56") (name "Net-(LED4-PadC)") (class "Default")
      (node (ref "LED4") (pin "C") (pinfunction "C_C") (pintype "passive"))
      (node (ref "R12") (pin "2") (pinfunction "2_2") (pintype "passive"))
    )
    (net (code "57") (name "Net-(LED5-PadA)") (class "Default")
      (node (ref "LED5") (pin "A") (pinfunction "A_A") (pintype "passive"))
      (node (ref "U6") (pin "GPIO4") (pinfunction "GPIO4_GPIO4") (pintype "bidirectional"))
    )
    (net (code "58") (name "Net-(LED5-PadC)") (class "Default")
      (node (ref "LED5") (pin "C") (pinfunction "C_C") (pintype "passive"))
      (node (ref "R21") (pin "2") (pinfunction "2_2") (pintype "passive"))
    )
    (net (code "59") (name "Net-(LED6-PadC)") (class "Default")
      (node (ref "LED6") (pin "C") (pinfunction "C_C") (pintype "passive"))
      (node (ref "R25") (pin "2") (pinfunction "2_2") (pintype "passive"))
    )
    (net (code "60") (name "Net-(LED7-PadA)") (class "Default")
      (node (ref "LED7") (pin "A") (pinfunction "A_A") (pintype "passive"))
      (node (ref "R2") (pin "2") (pinfunction "2_2") (pintype "passive"))
    )
    (net (code "61") (name "Net-(LED8-PadA)") (class "Default")
      (node (ref "LED8") (pin "A") (pinfunction "A_A") (pintype "passive"))
      (node (ref "R3") (pin "2") (pinfunction "2_2") (pintype "passive"))
    )
    (net (code "62") (name "Net-(LED9-PadA)") (class "Default")
      (node (ref "LED9") (pin "A") (pinfunction "A_A") (pintype "passive"))
      (node (ref "R4") (pin "2") (pinfunction "2_2") (pintype "passive"))
    )
    (net (code "63") (name "Net-(LED10-PadA)") (class "Default")
      (node (ref "LED10") (pin "A") (pinfunction "A_A") (pintype "passive"))
      (node (ref "R5") (pin "2") (pinfunction "2_2") (pintype "passive"))
    )
    (net (code "64") (name "Net-(LED11-PadA)") (class "Default")
      (node (ref "LED11") (pin "A") (pinfunction "A_A") (pintype "passive"))
      (node (ref "R6") (pin "2") (pinfunction "2_2") (pintype "passive"))
    )
    (net (code "65") (name "Net-(LED12-PadA)") (class "Default")
      (node (ref "LED12") (pin "A") (pinfunction "A_A") (pintype "passive"))
      (node (ref "R8") (pin "2") (pinfunction "2_2") (pintype "passive"))
    )
    (net (code "66") (name "Net-(LED13-PadA)") (class "Default")
      (node (ref "LED13") (pin "A") (pinfunction "A_A") (pintype "passive"))
      (node (ref "R9") (pin "2") (pinfunction "2_2") (pintype "passive"))
    )
    (net (code "67") (name "Net-(LED14-PadA)") (class "Default")
      (node (ref "LED14") (pin "A") (pinfunction "A_A") (pintype "passive"))
      (node (ref "R10") (pin "2") (pinfunction "2_2") (pintype "passive"))
    )
    (net (code "68") (name "Net-(R14-Pad2)") (class "Default")
      (node (ref "R14") (pin "2") (pinfunction "2_2") (pintype "passive"))
      (node (ref "U6") (pin "GPIO15") (pinfunction "GPIO15_GPIO15") (pintype "bidirectional"))
    )
    (net (code "69") (name "Net-(R30-Pad1)") (class "Default")
      (node (ref "R30") (pin "1") (pinfunction "1_1") (pintype "passive"))
      (node (ref "U6") (pin "CH_PD") (pinfunction "CH_PD_CH_PD") (pintype "bidirectional"))
    )
    (net (code "70") (name "Net-(U$1-CHANNELIN{slash}OUT0)") (class "Default")
      (node (ref "U$1") (pin "9") (pinfunction "CHANNELIN/OUT0_9") (pintype "bidirectional"))
      (node (ref "U1") (pin "1") (pinfunction "1B_1") (pintype "passive"))
    )
    (net (code "71") (name "Net-(U$1-CHANNELIN{slash}OUT1)") (class "Default")
      (node (ref "U$1") (pin "8") (pinfunction "CHANNELIN/OUT1_8") (pintype "bidirectional"))
      (node (ref "U1") (pin "2") (pinfunction "2B_2") (pintype "passive"))
    )
    (net (code "72") (name "Net-(U$1-CHANNELIN{slash}OUT2)") (class "Default")
      (node (ref "U$1") (pin "7") (pinfunction "CHANNELIN/OUT2_7") (pintype "bidirectional"))
      (node (ref "U1") (pin "3") (pinfunction "3B_3") (pintype "passive"))
    )
    (net (code "73") (name "Net-(U$1-CHANNELIN{slash}OUT3)") (class "Default")
      (node (ref "U$1") (pin "6") (pinfunction "CHANNELIN/OUT3_6") (pintype "bidirectional"))
      (node (ref "U1") (pin "4") (pinfunction "4B_4") (pintype "passive"))
    )
    (net (code "74") (name "Net-(U$1-CHANNELIN{slash}OUT4)") (class "Default")
      (node (ref "U$1") (pin "5") (pinfunction "CHANNELIN/OUT4_5") (pintype "bidirectional"))
      (node (ref "U1") (pin "5") (pinfunction "5B_5") (pintype "passive"))
    )
    (net (code "75") (name "Net-(U$1-CHANNELIN{slash}OUT5)") (class "Default")
      (node (ref "U$1") (pin "4") (pinfunction "CHANNELIN/OUT5_4") (pintype "bidirectional"))
      (node (ref "U1") (pin "6") (pinfunction "6B_6") (pintype "passive"))
    )
    (net (code "76") (name "Net-(U$1-CHANNELIN{slash}OUT6)") (class "Default")
      (node (ref "U$1") (pin "3") (pinfunction "CHANNELIN/OUT6_3") (pintype "bidirectional"))
      (node (ref "U1") (pin "7") (pinfunction "7B_7") (pintype "passive"))
    )
    (net (code "77") (name "Net-(U$1-CHANNELIN{slash}OUT7)") (class "Default")
      (node (ref "U$1") (pin "2") (pinfunction "CHANNELIN/OUT7_2") (pintype "bidirectional"))
      (node (ref "U1") (pin "8") (pinfunction "8B_8") (pintype "passive"))
    )
    (net (code "78") (name "Net-(U$1-CHANNELIN{slash}OUT8)") (class "Default")
      (node (ref "U$1") (pin "23") (pinfunction "CHANNELIN/OUT8_23") (pintype "bidirectional"))
      (node (ref "U2") (pin "1") (pinfunction "1B_1") (pintype "passive"))
    )
    (net (code "79") (name "Net-(U$1-CHANNELIN{slash}OUT9)") (class "Default")
      (node (ref "U$1") (pin "22") (pinfunction "CHANNELIN/OUT9_22") (pintype "bidirectional"))
      (node (ref "U2") (pin "2") (pinfunction "2B_2") (pintype "passive"))
    )
    (net (code "80") (name "Net-(U$1-CHANNELIN{slash}OUT10)") (class "Default")
      (node (ref "U$1") (pin "21") (pinfunction "CHANNELIN/OUT10_21") (pintype "bidirectional"))
      (node (ref "U2") (pin "3") (pinfunction "3B_3") (pintype "passive"))
    )
    (net (code "81") (name "Net-(U$1-CHANNELIN{slash}OUT11)") (class "Default")
      (node (ref "U$1") (pin "20") (pinfunction "CHANNELIN/OUT11_20") (pintype "bidirectional"))
      (node (ref "U2") (pin "4") (pinfunction "4B_4") (pintype "passive"))
    )
    (net (code "82") (name "Net-(U$1-CHANNELIN{slash}OUT12)") (class "Default")
      (node (ref "U$1") (pin "19") (pinfunction "CHANNELIN/OUT12_19") (pintype "bidirectional"))
      (node (ref "U2") (pin "5") (pinfunction "5B_5") (pintype "passive"))
    )
    (net (code "83") (name "Net-(U$1-CHANNELIN{slash}OUT13)") (class "Default")
      (node (ref "U$1") (pin "18") (pinfunction "CHANNELIN/OUT13_18") (pintype "bidirectional"))
      (node (ref "U2") (pin "6") (pinfunction "6B_6") (pintype "passive"))
    )
    (net (code "84") (name "Net-(U$1-CHANNELIN{slash}OUT14)") (class "Default")
      (node (ref "U$1") (pin "17") (pinfunction "CHANNELIN/OUT14_17") (pintype "bidirectional"))
      (node (ref "U2") (pin "7") (pinfunction "7B_7") (pintype "passive"))
    )
    (net (code "85") (name "Net-(U$1-CHANNELIN{slash}OUT15)") (class "Default")
      (node (ref "U$1") (pin "16") (pinfunction "CHANNELIN/OUT15_16") (pintype "bidirectional"))
      (node (ref "U2") (pin "8") (pinfunction "8B_8") (pintype "passive"))
    )
    (net (code "86") (name "Net-(U$3-BYP)") (class "Default")
      (node (ref "C2") (pin "1") (pinfunction "1_1") (pintype "passive"))
      (node (ref "U$3") (pin "4") (pinfunction "BYP_4") (pintype "passive"))
    )
    (net (code "87") (name "Net-(U$3-~{SHDN})") (class "Default")
      (node (ref "R1") (pin "1") (pinfunction "1_1") (pintype "passive"))
      (node (ref "U$3") (pin "3") (pinfunction "~{SHDN}_3") (pintype "passive"))
    )
    (net (code "88") (name "Net-(U1-1C)") (class "Default")
      (node (ref "U1") (pin "18") (pinfunction "1C_18") (pintype "passive"))
      (node (ref "X1") (pin "8") (pinfunction "1_8") (pintype "passive"))
    )
    (net (code "89") (name "Net-(U1-2C)") (class "Default")
      (node (ref "U1") (pin "17") (pinfunction "2C_17") (pintype "passive"))
      (node (ref "X1") (pin "7") (pinfunction "1_7") (pintype "passive"))
    )
    (net (code "90") (name "Net-(U1-3C)") (class "Default")
      (node (ref "U1") (pin "16") (pinfunction "3C_16") (pintype "passive"))
      (node (ref "X1") (pin "4") (pinfunction "1_4") (pintype "passive"))
    )
    (net (code "91") (name "Net-(U1-4C)") (class "Default")
      (node (ref "U1") (pin "15") (pinfunction "4C_15") (pintype "passive"))
      (node (ref "X1") (pin "5") (pinfunction "1_5") (pintype "passive"))
    )
    (net (code "92") (name "Net-(U1-5C)") (class "Default")
      (node (ref "U1") (pin "14") (pinfunction "5C_14") (pintype "passive"))
      (node (ref "X1") (pin "6") (pinfunction "1_6") (pintype "passive"))
    )
    (net (code "93") (name "Net-(U1-6C)") (class "Default")
      (node (ref "U1") (pin "13") (pinfunction "6C_13") (pintype "passive"))
      (node (ref "X1") (pin "13") (pinfunction "1_13") (pintype "passive"))
    )
    (net (code "94") (name "Net-(U1-7C)") (class "Default")
      (node (ref "U1") (pin "12") (pinfunction "7C_12") (pintype "passive"))
      (node (ref "X1") (pin "14") (pinfunction "1_14") (pintype "passive"))
    )
    (net (code "95") (name "Net-(U1-8C)") (class "Default")
      (node (ref "U1") (pin "11") (pinfunction "8C_11") (pintype "passive"))
      (node (ref "X1") (pin "15") (pinfunction "1_15") (pintype "passive"))
    )
    (net (code "96") (name "Net-(U2-1C)") (class "Default")
      (node (ref "U2") (pin "18") (pinfunction "1C_18") (pintype "passive"))
      (node (ref "X1") (pin "12") (pinfunction "1_12") (pintype "passive"))
    )
    (net (code "97") (name "Net-(U2-2C)") (class "Default")
      (node (ref "U2") (pin "17") (pinfunction "2C_17") (pintype "passive"))
      (node (ref "X1") (pin "11") (pinfunction "1_11") (pintype "passive"))
    )
    (net (code "98") (name "Net-(U2-3C)") (class "Default")
      (node (ref "U2") (pin "16") (pinfunction "3C_16") (pintype "passive"))
      (node (ref "X1") (pin "10") (pinfunction "1_10") (pintype "passive"))
    )
    (net (code "99") (name "Net-(U2-4C)") (class "Default")
      (node (ref "U2") (pin "15") (pinfunction "4C_15") (pintype "passive"))
      (node (ref "X1") (pin "9") (pinfunction "1_9") (pintype "passive"))
    )
    (net (code "100") (name "Net-(U7-PB6(XTAL1{slash}TOSC1))") (class "Default")
      (node (ref "U7") (pin "7") (pinfunction "PB6(XTAL1/TOSC1)_7") (pintype "bidirectional"))
      (node (ref "Y1") (pin "1") (pinfunction "1_1") (pintype "passive"))
    )
    (net (code "101") (name "Net-(U7-PB7(XTAL2{slash}TOSC2))") (class "Default")
      (node (ref "U7") (pin "8") (pinfunction "PB7(XTAL2/TOSC2)_8") (pintype "bidirectional"))
      (node (ref "Y1") (pin "3") (pinfunction "3_3") (pintype "passive"))
    )
    (net (code "102") (name "Net-(U7-PC4(ADC4{slash}SDA))") (class "Default")
      (node (ref "LED6") (pin "A") (pinfunction "A_A") (pintype "passive"))
      (node (ref "U7") (pin "27") (pinfunction "PC4(ADC4/SDA)_27") (pintype "bidirectional"))
    )
    (net (code "103") (name "Net-(U11-COMPARATORINVERTINGINPUT)") (class "Default")
      (node (ref "R34") (pin "2") (pinfunction "2_2") (pintype "passive"))
      (node (ref "R36") (pin "2") (pinfunction "2_2") (pintype "passive"))
      (node (ref "U11") (pin "5") (pinfunction "COMPARATORINVERTINGINPUT_5") (pintype "passive"))
    )
    (net (code "104") (name "Net-(U11-DRIVERCOLLECTOR)") (class "Default")
      (node (ref "R33") (pin "1") (pinfunction "1_1") (pintype "passive"))
      (node (ref "U11") (pin "8") (pinfunction "DRIVERCOLLECTOR_8") (pintype "passive"))
    )
    (net (code "105") (name "Net-(U11-TIMINGCAPACITOR)") (class "Default")
      (node (ref "C25") (pin "2") (pinfunction "2_2") (pintype "passive"))
      (node (ref "U11") (pin "3") (pinfunction "TIMINGCAPACITOR_3") (pintype "passive"))
    )
    (net (code "106") (name "VCC") (class "Default")
      (node (ref "C20") (pin "+") (pinfunction "+_+") (pintype "passive"))
      (node (ref "C21") (pin "1") (pinfunction "1_1") (pintype "passive"))
      (node (ref "C22") (pin "1") (pinfunction "1_1") (pintype "passive"))
      (node (ref "C23") (pin "1") (pinfunction "1_1") (pintype "passive"))
      (node (ref "C24") (pin "2") (pinfunction "2_2") (pintype "passive"))
      (node (ref "C5") (pin "1") (pinfunction "1_1") (pintype "passive"))
      (node (ref "R35") (pin "2") (pinfunction "2_2") (pintype "passive"))
      (node (ref "U11") (pin "6") (pinfunction "VCC_6") (pintype "power_in"))
      (node (ref "U3") (pin "1") (pinfunction "INPUT_1") (pintype "input"))
      (node (ref "U8") (pin "1") (pinfunction "1_1") (pintype "passive"))
    )
    (net (code "107") (name "unconnected-(IC1-I5-Pad5)") (class "Default")
      (node (ref "IC1") (pin "5") (pinfunction "I5_5") (pintype "input"))
    )
    (net (code "108") (name "unconnected-(IC1-I6-Pad6)") (class "Default")
      (node (ref "IC1") (pin "6") (pinfunction "I6_6") (pintype "input"))
    )
    (net (code "109") (name "unconnected-(IC1-I7-Pad7)") (class "Default")
      (node (ref "IC1") (pin "7") (pinfunction "I7_7") (pintype "input"))
    )
    (net (code "110") (name "unconnected-(IC1-O5-Pad12)") (class "Default")
      (node (ref "IC1") (pin "12") (pinfunction "O5_12") (pintype "open_collector"))
    )
    (net (code "111") (name "unconnected-(IC1-O6-Pad11)") (class "Default")
      (node (ref "IC1") (pin "11") (pinfunction "O6_11") (pintype "open_collector"))
    )
    (net (code "112") (name "unconnected-(IC1-O7-Pad10)") (class "Default")
      (node (ref "IC1") (pin "10") (pinfunction "O7_10") (pintype "open_collector"))
    )
    (net (code "113") (name "unconnected-(IC2-I5-Pad5)") (class "Default")
      (node (ref "IC2") (pin "5") (pinfunction "I5_5") (pintype "input"))
    )
    (net (code "114") (name "unconnected-(IC2-I6-Pad6)") (class "Default")
      (node (ref "IC2") (pin "6") (pinfunction "I6_6") (pintype "input"))
    )
    (net (code "115") (name "unconnected-(IC2-I7-Pad7)") (class "Default")
      (node (ref "IC2") (pin "7") (pinfunction "I7_7") (pintype "input"))
    )
    (net (code "116") (name "unconnected-(IC2-O5-Pad12)") (class "Default")
      (node (ref "IC2") (pin "12") (pinfunction "O5_12") (pintype "open_collector"))
    )
    (net (code "117") (name "unconnected-(IC2-O6-Pad11)") (class "Default")
      (node (ref "IC2") (pin "11") (pinfunction "O6_11") (pintype "open_collector"))
    )
    (net (code "118") (name "unconnected-(IC2-O7-Pad10)") (class "Default")
      (node (ref "IC2") (pin "10") (pinfunction "O7_10") (pintype "open_collector"))
    )
    (net (code "119") (name "unconnected-(J10-Pad2)") (class "Default")
      (node (ref "J10") (pin "2") (pinfunction "2_2") (pintype "passive"))
    )
    (net (code "120") (name "unconnected-(J12-Pad2)") (class "Default")
      (node (ref "J12") (pin "2") (pinfunction "2_2") (pintype "passive"))
    )
    (net (code "121") (name "unconnected-(U2-5C-Pad14)") (class "Default")
      (node (ref "U2") (pin "14") (pinfunction "5C_14") (pintype "passive"))
    )
    (net (code "122") (name "unconnected-(U2-6C-Pad13)") (class "Default")
      (node (ref "U2") (pin "13") (pinfunction "6C_13") (pintype "passive"))
    )
    (net (code "123") (name "unconnected-(U2-7C-Pad12)") (class "Default")
      (node (ref "U2") (pin "12") (pinfunction "7C_12") (pintype "passive"))
    )
    (net (code "124") (name "unconnected-(U2-8C-Pad11)") (class "Default")
      (node (ref "U2") (pin "11") (pinfunction "8C_11") (pintype "passive"))
    )
    (net (code "125") (name "unconnected-(U6-*GPIO9-PadGPIO9)") (class "Default")
      (node (ref "U6") (pin "GPIO9") (pinfunction "*GPIO9_GPIO9") (pintype "bidirectional"))
    )
    (net (code "126") (name "unconnected-(U6-*GPIO10-PadGPIO10)") (class "Default")
      (node (ref "U6") (pin "GPIO10") (pinfunction "*GPIO10_GPIO10") (pintype "bidirectional"))
    )
    (net (code "127") (name "unconnected-(U6-PadADC)") (class "Default")
      (node (ref "U6") (pin "ADC") (pinfunction "ADC_ADC") (pintype "bidirectional"))
    )
    (net (code "128") (name "unconnected-(U6-PadCS0)") (class "Default")
      (node (ref "U6") (pin "CS0") (pinfunction "CS0_CS0") (pintype "bidirectional"))
    )
    (net (code "129") (name "unconnected-(U6-PadGPIO5)") (class "Default")
      (node (ref "U6") (pin "GPIO5") (pinfunction "GPIO5_GPIO5") (pintype "bidirectional"))
    )
    (net (code "130") (name "unconnected-(U6-PadMISO)") (class "Default")
      (node (ref "U6") (pin "MISO") (pinfunction "MISO_MISO") (pintype "bidirectional"))
    )
    (net (code "131") (name "unconnected-(U6-PadMOSI)") (class "Default")
      (node (ref "U6") (pin "MOSI") (pinfunction "MOSI_MOSI") (pintype "bidirectional"))
    )
    (net (code "132") (name "unconnected-(U6-PadSCLK)") (class "Default")
      (node (ref "U6") (pin "SCLK") (pinfunction "SCLK_SCLK") (pintype "bidirectional"))
    )
    (net (code "133") (name "unconnected-(U7-ADC6-Pad19)") (class "Default")
      (node (ref "U7") (pin "19") (pinfunction "ADC6_19") (pintype "bidirectional"))
    )
    (net (code "134") (name "unconnected-(U7-ADC7-Pad22)") (class "Default")
      (node (ref "U7") (pin "22") (pinfunction "ADC7_22") (pintype "bidirectional"))
    )
    (net (code "135") (name "unconnected-(U7-AREF-Pad20)") (class "Default")
      (node (ref "U7") (pin "20") (pinfunction "AREF_20") (pintype "bidirectional"))
    )
    (net (code "136") (name "unconnected-(U7-PC5(ADC5{slash}SCL)-Pad28)") (class "Default")
      (node (ref "U7") (pin "28") (pinfunction "PC5(ADC5/SCL)_28") (pintype "bidirectional"))
    )
    (net (code "137") (name "unconnected-(U8-Pad3)") (class "Default")
      (node (ref "U8") (pin "3") (pinfunction "3_3") (pintype "passive"))
    )
    (net (code "138") (name "unconnected-(X1-Pad1)") (class "Default")
      (node (ref "X1") (pin "1") (pinfunction "1_1") (pintype "passive"))
    )
    (net (code "139") (name "unconnected-(X1I-1-Pad2)") (class "Default")
      (node (ref "X1") (pin "2") (pinfunction "1_2") (pintype "passive"))
    )
  )
)
